# ac_dc_converter.net
KiCad netlist of a schematic drawn in EAGLE
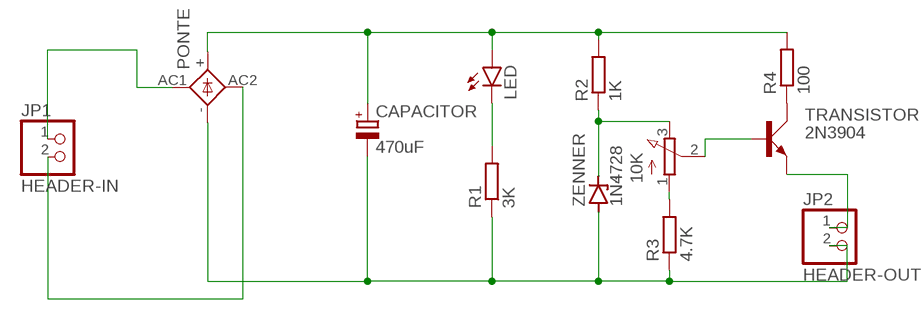
[diagram p0: schematic, sheet 1]

(export (version "E")
  (design (tool "Eeschema 10.0.6"))
  (components
    (comp (ref "CAPACITOR")
      (value "470uF")
      (footprint "eagle-import:E5-10,5")
      (libsource (lib "eagle-import") (part "CPOL-EUE5-10.5"))
    )
    (comp (ref "JP1")
      (value "HEADER-IN")
      (footprint "eagle-import:1X02")
      (libsource (lib "eagle-import") (part "PINHD-1X2"))
    )
    (comp (ref "JP2")
      (value "HEADER-OUT")
      (footprint "eagle-import:1X02")
      (libsource (lib "eagle-import") (part "PINHD-1X2"))
    )
    (comp (ref "LED")
      (value "LED5MM")
      (footprint "eagle-import:LED5MM")
      (libsource (lib "eagle-import") (part "LED5MM"))
    )
    (comp (ref "PONTE")
      (value "1KAB")
      (footprint "eagle-import:1KAB")
      (libsource (lib "eagle-import") (part "1KAB"))
    )
    (comp (ref "R1")
      (value "3K")
      (footprint "eagle-import:0204_7")
      (libsource (lib "eagle-import") (part "R-EU_0204/7"))
    )
    (comp (ref "R2")
      (value "1K")
      (footprint "eagle-import:0204_7")
      (libsource (lib "eagle-import") (part "R-EU_0204/7"))
    )
    (comp (ref "R3")
      (value "4.7K")
      (footprint "eagle-import:0204_7")
      (libsource (lib "eagle-import") (part "R-EU_0204/7"))
    )
    (comp (ref "R4")
      (value "100")
      (footprint "eagle-import:0204_7")
      (libsource (lib "eagle-import") (part "R-EU_0204/7"))
    )
    (comp (ref "TRANSISTOR")
      (value "2N3904")
      (footprint "eagle-import:TO92D")
      (libsource (lib "eagle-import") (part "2N3904"))
    )
    (comp (ref "ZENNER")
      (value "1N4728")
      (footprint "eagle-import:DO41Z10")
      (libsource (lib "eagle-import") (part "1N4728"))
    )
    (comp (ref "¨")
      (value "10K")
      (footprint "eagle-import:3RP_1610N")
      (libsource (lib "eagle-import") (part "3RP/1610N"))
    )
  )
  (nets
    (net (code "1") (name "Net-(CAPACITOR-Pad+)") (class "Default")
      (node (ref "CAPACITOR") (pin "+") (pinfunction "+_+") (pintype "passive"))
      (node (ref "LED") (pin "A") (pinfunction "A_A") (pintype "passive"))
      (node (ref "PONTE") (pin "+") (pinfunction "+_+") (pintype "passive"))
      (node (ref "R2") (pin "2") (pinfunction "2_2") (pintype "passive"))
      (node (ref "R4") (pin "2") (pinfunction "2_2") (pintype "passive"))
    )
    (net (code "2") (name "Net-(CAPACITOR-Pad-)") (class "Default")
      (node (ref "CAPACITOR") (pin "-") (pinfunction "-_-") (pintype "passive"))
      (node (ref "JP2") (pin "2") (pinfunction "2_2") (pintype "passive"))
      (node (ref "PONTE") (pin "-") (pinfunction "-_-") (pintype "passive"))
      (node (ref "R1") (pin "1") (pinfunction "1_1") (pintype "passive"))
      (node (ref "R3") (pin "1") (pinfunction "1_1") (pintype "passive"))
      (node (ref "ZENNER") (pin "A") (pinfunction "A_A") (pintype "passive"))
    )
    (net (code "3") (name "Net-(JP1-Pad1)") (class "Default")
      (node (ref "JP1") (pin "1") (pinfunction "1_1") (pintype "passive"))
      (node (ref "PONTE") (pin "AC1") (pinfunction "AC1_AC1") (pintype "passive"))
    )
    (net (code "4") (name "Net-(JP1-Pad2)") (class "Default")
      (node (ref "JP1") (pin "2") (pinfunction "2_2") (pintype "passive"))
      (node (ref "PONTE") (pin "AC2") (pinfunction "AC2_AC2") (pintype "passive"))
    )
    (net (code "5") (name "Net-(JP2-Pad1)") (class "Default")
      (node (ref "JP2") (pin "1") (pinfunction "1_1") (pintype "passive"))
      (node (ref "TRANSISTOR") (pin "E") (pinfunction "E_E") (pintype "passive"))
    )
    (net (code "6") (name "Net-(LED-C)") (class "Default")
      (node (ref "LED") (pin "K") (pinfunction "C_K") (pintype "passive"))
      (node (ref "R1") (pin "2") (pinfunction "2_2") (pintype "passive"))
    )
    (net (code "7") (name "Net-(R4-Pad1)") (class "Default")
      (node (ref "R4") (pin "1") (pinfunction "1_1") (pintype "passive"))
      (node (ref "TRANSISTOR") (pin "C") (pinfunction "C_C") (pintype "passive"))
    )
    (net (code "8") (name "Net-(¨-A)") (class "Default")
      (node (ref "R3") (pin "2") (pinfunction "2_2") (pintype "passive"))
      (node (ref "¨") (pin "1") (pinfunction "A_1") (pintype "passive"))
    )
    (net (code "9") (name "Net-(¨-E)") (class "Default")
      (node (ref "R2") (pin "1") (pinfunction "1_1") (pintype "passive"))
      (node (ref "ZENNER") (pin "C") (pinfunction "C_C") (pintype "passive"))
      (node (ref "¨") (pin "3") (pinfunction "E_3") (pintype "passive"))
    )
    (net (code "10") (name "Net-(¨-S)") (class "Default")
      (node (ref "TRANSISTOR") (pin "B") (pinfunction "B_B") (pintype "passive"))
      (node (ref "¨") (pin "2") (pinfunction "S_2") (pintype "passive"))
    )
  )
)
